# 3_waffling60-MXHS-ANSI_mcu.net
KiCad netlist of a schematic drawn in Altium Designer
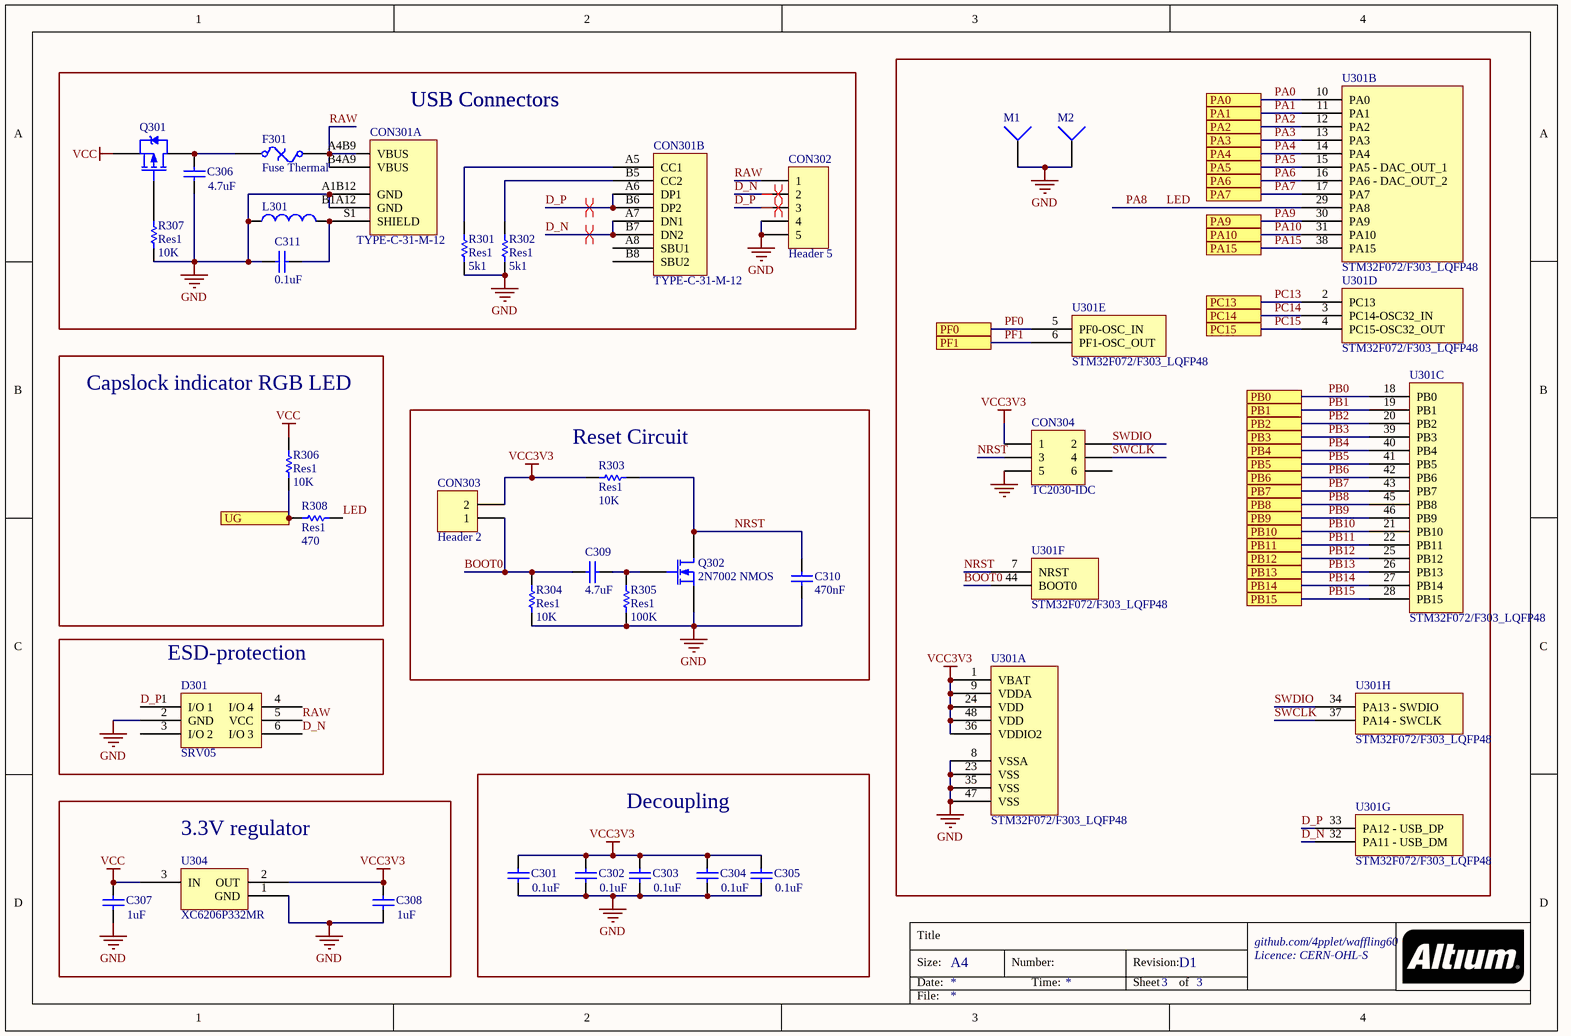
[diagram p0: 3_waffling60-MXHS-ANSI_mcu.SchDoc]

(export (version "E")
  (design (tool "Eeschema 10.0.6"))
  (components
    (comp (ref "C301")
      (value "0.1uF")
      (footprint "C0603[1608]")
      (description "Capacitor")
      (fields (field (name "LCSC PART #") "C14663") (field (name "MRF.PART") "CC0603KRX7R9BB104"))
      (libsource (lib "Miscellaneous Devices") (part "Cap"))
    )
    (comp (ref "C302")
      (value "0.1uF")
      (footprint "C0603[1608]")
      (description "Capacitor")
      (fields (field (name "LCSC PART #") "C14663") (field (name "MRF.PART") "CC0603KRX7R9BB104"))
      (libsource (lib "Miscellaneous Devices") (part "Cap"))
    )
    (comp (ref "C303")
      (value "0.1uF")
      (footprint "C0603[1608]")
      (description "Capacitor")
      (fields (field (name "LCSC PART #") "C14663") (field (name "MRF.PART") "CC0603KRX7R9BB104"))
      (libsource (lib "Miscellaneous Devices") (part "Cap"))
    )
    (comp (ref "C304")
      (value "0.1uF")
      (footprint "C0603[1608]")
      (description "Capacitor")
      (fields (field (name "LCSC PART #") "C14663") (field (name "MRF.PART") "CC0603KRX7R9BB104"))
      (libsource (lib "Miscellaneous Devices") (part "Cap"))
    )
    (comp (ref "C305")
      (value "0.1uF")
      (footprint "C0603[1608]")
      (description "Capacitor")
      (fields (field (name "LCSC PART #") "C14663") (field (name "MRF.PART") "CC0603KRX7R9BB104"))
      (libsource (lib "Miscellaneous Devices") (part "Cap"))
    )
    (comp (ref "C306")
      (value "4.7uF")
      (footprint "C0603[1608]")
      (description "Capacitor")
      (fields (field (name "LCSC PART #") "C19666") (field (name "MRF.PART") "CL10A475KO8NNNC"))
      (libsource (lib "Miscellaneous Devices") (part "Cap"))
    )
    (comp (ref "C307")
      (value "1uF")
      (footprint "C0603[1608]")
      (description "Capacitor")
      (fields (field (name "LCSC PART #") "C15849") (field (name "MRF.PART") "CL10A105KB8NNNC"))
      (libsource (lib "Miscellaneous Devices") (part "Cap"))
    )
    (comp (ref "C308")
      (value "1uF")
      (footprint "C0603[1608]")
      (description "Capacitor")
      (fields (field (name "LCSC PART #") "C15849") (field (name "MRF.PART") "CL10A105KB8NNNC"))
      (libsource (lib "Miscellaneous Devices") (part "Cap"))
    )
    (comp (ref "C309")
      (value "4.7uF")
      (footprint "C0603[1608]")
      (description "Capacitor")
      (fields (field (name "LCSC PART #") "C19666") (field (name "MRF.PART") "CL10A475KO8NNNC"))
      (libsource (lib "Miscellaneous Devices") (part "Cap"))
    )
    (comp (ref "C310")
      (value "470nF")
      (footprint "C0603[1608]")
      (description "Capacitor")
      (fields (field (name "LCSC PART #") "C1623") (field (name "MRF.PART") "CL10B474KA8NNNC"))
      (libsource (lib "Miscellaneous Devices") (part "Cap"))
    )
    (comp (ref "C311")
      (value "0.1uF")
      (footprint "C0603[1608]")
      (description "Capacitor")
      (fields (field (name "LCSC PART #") "C14663") (field (name "MRF.PART") "CC0603KRX7R9BB104"))
      (libsource (lib "Miscellaneous Devices") (part "Cap"))
    )
    (comp (ref "CON301")
      (value "TYPE-C-31-M-12")
      (footprint "TYPE-C-31-M-12")
      (fields (field (name "LCSC PART #") "C165948"))
      (libsource (lib "Schlib1") (part "TYPE-C-31-M-12"))
    )
    (comp (ref "CON302")
      (value "Header 5")
      (footprint "UDB_combo_JST_MOLEX")
      (description "JST for USB daughter board")
      (fields (field (name "LCSC PART #") "C145956"))
      (libsource (lib "Miscellaneous Connectors") (part "Header 5"))
    )
    (comp (ref "CON303")
      (value "Header 2")
      (footprint "HDR1X2")
      (description "Header, 2-Pin")
      (libsource (lib "Miscellaneous Connectors") (part "Header 2"))
    )
    (comp (ref "CON304")
      (value "TC2030-IDC")
      (footprint "TC2030-IDC-NL")
      (description "Header, 3-Pin, Dual row")
      (libsource (lib "Miscellaneous Connectors") (part "Header 3X2"))
    )
    (comp (ref "D301")
      (value "SRV05")
      (footprint "SOT-23-6")
      (fields (field (name "LCSC PART #") "C85364") (field (name "MRF.PART") "SRV05-4-P-T7"))
      (libsource (lib "Keebs") (part "SRV05"))
    )
    (comp (ref "F301")
      (value "Fuse Thermal")
      (footprint "C1206[3216]")
      (description "Thermal Fuse")
      (fields (field (name "LCSC PART #") "C135338") (field (name "MRF.PART") "ASMD1206-050"))
      (libsource (lib "Miscellaneous Devices") (part "Fuse Thermal"))
    )
    (comp (ref "L301")
      (value "Inductor")
      (footprint "L0805")
      (fields (field (name "LCSC PART #") "C1015") (field (name "MRF.PART") "GZ2012D101TF"))
      (libsource (lib "Simulation Generic Components") (part "Inductor"))
    )
    (comp (ref "M1")
      (value "Socket")
      (footprint "mounting_hole")
      (libsource (lib "Miscellaneous Connectors") (part "Socket"))
    )
    (comp (ref "M2")
      (value "Socket")
      (footprint "mounting_hole")
      (libsource (lib "Miscellaneous Connectors") (part "Socket"))
    )
    (comp (ref "Q301")
      (value "PMOS-2")
      (footprint "SOT-23-3")
      (description "P-Channel Power MOSFET")
      (fields (field (name "LCSC PART #") "C10487") (field (name "MRF.PART") "SI2301CDS-T1-GE3"))
      (libsource (lib "Miscellaneous Devices") (part "PMOS-2"))
    )
    (comp (ref "Q302")
      (value "2N7002 NMOS")
      (footprint "SOT-23-3")
      (description "N-Channel MOSFET")
      (fields (field (name "LCSC PART #") "C8545") (field (name "MRF.PART") "2N7002"))
      (libsource (lib "Miscellaneous Devices") (part "MOSFET-N"))
    )
    (comp (ref "R301")
      (value "Res1")
      (footprint "R0603[1608]")
      (description "Resistor")
      (fields
        (field (name "ALTIUM_VALUE") "5k1")
        (field (name "LCSC PART #") "C23186")
        (field (name "MRF.PART") "0603WAF5101T5E")
      )
      (libsource (lib "Miscellaneous Devices") (part "Res1"))
    )
    (comp (ref "R302")
      (value "Res1")
      (footprint "R0603[1608]")
      (description "Resistor")
      (fields
        (field (name "ALTIUM_VALUE") "5k1")
        (field (name "LCSC PART #") "C23186")
        (field (name "MRF.PART") "0603WAF5101T5E")
      )
      (libsource (lib "Miscellaneous Devices") (part "Res1"))
    )
    (comp (ref "R303")
      (value "Res1")
      (footprint "R0603[1608]")
      (description "Resistor")
      (fields
        (field (name "ALTIUM_VALUE") "10K")
        (field (name "LCSC PART #") "C25804")
        (field (name "MRF.PART") "0603WAF1002T5E")
      )
      (libsource (lib "Miscellaneous Devices") (part "Res1"))
    )
    (comp (ref "R304")
      (value "Res1")
      (footprint "R0603[1608]")
      (description "Resistor")
      (fields
        (field (name "ALTIUM_VALUE") "10K")
        (field (name "LCSC PART #") "C25804")
        (field (name "MRF.PART") "0603WAF1002T5E")
      )
      (libsource (lib "Miscellaneous Devices") (part "Res1"))
    )
    (comp (ref "R305")
      (value "Res1")
      (footprint "R0603[1608]")
      (description "Resistor")
      (fields
        (field (name "ALTIUM_VALUE") "100K")
        (field (name "LCSC PART #") "C25803")
        (field (name "MRF.PART") "0603WAF1003T5E")
      )
      (libsource (lib "Miscellaneous Devices") (part "Res1"))
    )
    (comp (ref "R306")
      (value "Res1")
      (footprint "R0603[1608]")
      (description "Resistor")
      (fields
        (field (name "ALTIUM_VALUE") "10K")
        (field (name "LCSC PART #") "C25804")
        (field (name "MRF.PART") "0603WAF1002T5E")
      )
      (libsource (lib "Miscellaneous Devices") (part "Res1"))
    )
    (comp (ref "R307")
      (value "Res1")
      (footprint "R0603[1608]")
      (description "Resistor")
      (fields
        (field (name "ALTIUM_VALUE") "10K")
        (field (name "LCSC PART #") "C25804")
        (field (name "MRF.PART") "0603WAF1002T5E")
      )
      (libsource (lib "Miscellaneous Devices") (part "Res1"))
    )
    (comp (ref "R308")
      (value "Res1")
      (footprint "R0603[1608]")
      (description "Resistor")
      (fields
        (field (name "ALTIUM_VALUE") "470")
        (field (name "LCSC PART #") "C23179")
        (field (name "MRF.PART") "0603WAF4700T5E")
      )
      (libsource (lib "Miscellaneous Devices") (part "Res1"))
    )
    (comp (ref "U301")
      (value "STM32F072/F303_LQFP48")
      (footprint "STM32 - COMBO 7X7MM")
      (fields (field (name "LCSC PART #") "C915660") (field (name "MRF.PART") "APM32F072CBT6"))
      (libsource (lib "Keebs") (part "STM32F072/F303_LQFP48"))
    )
    (comp (ref "U304")
      (value "XC6206P332MR")
      (footprint "SOT-23-3")
      (fields (field (name "LCSC PART #") "C5446"))
      (libsource (lib "Keebs") (part "SOT23 LDO"))
    )
  )
  (nets
    (net (code "1") (name "/BOOT0") (class "Default")
      (node (ref "C309") (pin "1") (pinfunction "1_1") (pintype "passive"))
      (node (ref "CON303") (pin "1") (pinfunction "1_1") (pintype "passive"))
      (node (ref "R304") (pin "1") (pinfunction "1_1") (pintype "passive"))
      (node (ref "U301") (pin "44") (pinfunction "BOOT0_44") (pintype "passive"))
    )
    (net (code "2") (name "/D_N") (class "Default")
      (node (ref "CON301") (pin "A7") (pinfunction "DN1_A7") (pintype "passive"))
      (node (ref "CON301") (pin "B7") (pinfunction "DN2_B7") (pintype "passive"))
      (node (ref "CON302") (pin "2") (pinfunction "2_2") (pintype "passive"))
      (node (ref "D301") (pin "6") (pinfunction "I/O_3_6") (pintype "passive"))
      (node (ref "U301") (pin "32") (pinfunction "PA11_-_USB_DM_32") (pintype "passive"))
    )
    (net (code "3") (name "/D_P") (class "Default")
      (node (ref "CON301") (pin "A6") (pinfunction "DP1_A6") (pintype "passive"))
      (node (ref "CON301") (pin "B6") (pinfunction "DP2_B6") (pintype "passive"))
      (node (ref "CON302") (pin "3") (pinfunction "3_3") (pintype "passive"))
      (node (ref "D301") (pin "1") (pinfunction "I/O_1_1") (pintype "passive"))
      (node (ref "U301") (pin "33") (pinfunction "PA12_-_USB_DP_33") (pintype "passive"))
    )
    (net (code "4") (name "/LED") (class "Default")
      (node (ref "R308") (pin "2") (pinfunction "2_2") (pintype "passive"))
      (node (ref "U301") (pin "29") (pinfunction "PA8_29") (pintype "passive"))
    )
    (net (code "5") (name "/NRST") (class "Default")
      (node (ref "C310") (pin "1") (pinfunction "1_1") (pintype "passive"))
      (node (ref "CON304") (pin "3") (pinfunction "3_3") (pintype "passive"))
      (node (ref "Q302") (pin "3") (pinfunction "D_3") (pintype "passive"))
      (node (ref "R303") (pin "2") (pinfunction "2_2") (pintype "passive"))
      (node (ref "U301") (pin "7") (pinfunction "NRST_7") (pintype "passive"))
    )
    (net (code "6") (name "/PA0") (class "Default")
      (node (ref "U301") (pin "10") (pinfunction "PA0_10") (pintype "passive"))
    )
    (net (code "7") (name "/PA1") (class "Default")
      (node (ref "U301") (pin "11") (pinfunction "PA1_11") (pintype "passive"))
    )
    (net (code "8") (name "/PA2") (class "Default")
      (node (ref "U301") (pin "12") (pinfunction "PA2_12") (pintype "passive"))
    )
    (net (code "9") (name "/PA3") (class "Default")
      (node (ref "U301") (pin "13") (pinfunction "PA3_13") (pintype "passive"))
    )
    (net (code "10") (name "/PA4") (class "Default")
      (node (ref "U301") (pin "14") (pinfunction "PA4_14") (pintype "passive"))
    )
    (net (code "11") (name "/PA5") (class "Default")
      (node (ref "U301") (pin "15") (pinfunction "PA5_-_DAC_OUT_1_15") (pintype "passive"))
    )
    (net (code "12") (name "/PA6") (class "Default")
      (node (ref "U301") (pin "16") (pinfunction "PA6_-_DAC_OUT_2_16") (pintype "passive"))
    )
    (net (code "13") (name "/PA7") (class "Default")
      (node (ref "U301") (pin "17") (pinfunction "PA7_17") (pintype "passive"))
    )
    (net (code "14") (name "/PA9") (class "Default")
      (node (ref "U301") (pin "30") (pinfunction "PA9_30") (pintype "passive"))
    )
    (net (code "15") (name "/PA10") (class "Default")
      (node (ref "U301") (pin "31") (pinfunction "PA10_31") (pintype "passive"))
    )
    (net (code "16") (name "/PA15") (class "Default")
      (node (ref "U301") (pin "38") (pinfunction "PA15_38") (pintype "passive"))
    )
    (net (code "17") (name "/PB0") (class "Default")
      (node (ref "U301") (pin "18") (pinfunction "PB0_18") (pintype "passive"))
    )
    (net (code "18") (name "/PB1") (class "Default")
      (node (ref "U301") (pin "19") (pinfunction "PB1_19") (pintype "passive"))
    )
    (net (code "19") (name "/PB2") (class "Default")
      (node (ref "U301") (pin "20") (pinfunction "PB2_20") (pintype "passive"))
    )
    (net (code "20") (name "/PB3") (class "Default")
      (node (ref "U301") (pin "39") (pinfunction "PB3_39") (pintype "passive"))
    )
    (net (code "21") (name "/PB4") (class "Default")
      (node (ref "U301") (pin "40") (pinfunction "PB4_40") (pintype "passive"))
    )
    (net (code "22") (name "/PB5") (class "Default")
      (node (ref "U301") (pin "41") (pinfunction "PB5_41") (pintype "passive"))
    )
    (net (code "23") (name "/PB6") (class "Default")
      (node (ref "U301") (pin "42") (pinfunction "PB6_42") (pintype "passive"))
    )
    (net (code "24") (name "/PB7") (class "Default")
      (node (ref "U301") (pin "43") (pinfunction "PB7_43") (pintype "passive"))
    )
    (net (code "25") (name "/PB8") (class "Default")
      (node (ref "U301") (pin "45") (pinfunction "PB8_45") (pintype "passive"))
    )
    (net (code "26") (name "/PB9") (class "Default")
      (node (ref "U301") (pin "46") (pinfunction "PB9_46") (pintype "passive"))
    )
    (net (code "27") (name "/PB10") (class "Default")
      (node (ref "U301") (pin "21") (pinfunction "PB10_21") (pintype "passive"))
    )
    (net (code "28") (name "/PB11") (class "Default")
      (node (ref "U301") (pin "22") (pinfunction "PB11_22") (pintype "passive"))
    )
    (net (code "29") (name "/PB12") (class "Default")
      (node (ref "U301") (pin "25") (pinfunction "PB12_25") (pintype "passive"))
    )
    (net (code "30") (name "/PB13") (class "Default")
      (node (ref "U301") (pin "26") (pinfunction "PB13_26") (pintype "passive"))
    )
    (net (code "31") (name "/PB14") (class "Default")
      (node (ref "U301") (pin "27") (pinfunction "PB14_27") (pintype "passive"))
    )
    (net (code "32") (name "/PB15") (class "Default")
      (node (ref "U301") (pin "28") (pinfunction "PB15_28") (pintype "passive"))
    )
    (net (code "33") (name "/PC13") (class "Default")
      (node (ref "U301") (pin "2") (pinfunction "PC13_2") (pintype "passive"))
    )
    (net (code "34") (name "/PC14") (class "Default")
      (node (ref "U301") (pin "3") (pinfunction "PC14-OSC32_IN_3") (pintype "passive"))
    )
    (net (code "35") (name "/PC15") (class "Default")
      (node (ref "U301") (pin "4") (pinfunction "PC15-OSC32_OUT_4") (pintype "passive"))
    )
    (net (code "36") (name "/PF0") (class "Default")
      (node (ref "U301") (pin "5") (pinfunction "PF0-OSC_IN_5") (pintype "passive"))
    )
    (net (code "37") (name "/PF1") (class "Default")
      (node (ref "U301") (pin "6") (pinfunction "PF1-OSC_OUT_6") (pintype "passive"))
    )
    (net (code "38") (name "/RAW") (class "Default")
      (node (ref "CON301") (pin "A4B9") (pinfunction "VBUS_A4B9") (pintype "passive"))
      (node (ref "CON301") (pin "B4A9") (pinfunction "VBUS_B4A9") (pintype "passive"))
      (node (ref "CON302") (pin "1") (pinfunction "1_1") (pintype "passive"))
      (node (ref "D301") (pin "5") (pinfunction "VCC_5") (pintype "passive"))
      (node (ref "F301") (pin "2") (pinfunction "2_2") (pintype "passive"))
    )
    (net (code "39") (name "/SWCLK") (class "Default")
      (node (ref "CON304") (pin "4") (pinfunction "4_4") (pintype "passive"))
      (node (ref "U301") (pin "37") (pinfunction "PA14_-_SWCLK_37") (pintype "passive"))
    )
    (net (code "40") (name "/SWDIO") (class "Default")
      (node (ref "CON304") (pin "2") (pinfunction "2_2") (pintype "passive"))
      (node (ref "U301") (pin "34") (pinfunction "PA13_-_SWDIO_34") (pintype "passive"))
    )
    (net (code "41") (name "/UG") (class "Default")
      (node (ref "R306") (pin "2") (pinfunction "2_2") (pintype "passive"))
      (node (ref "R308") (pin "1") (pinfunction "1_1") (pintype "passive"))
    )
    (net (code "42") (name "GND") (class "Default")
      (node (ref "C301") (pin "1") (pinfunction "1_1") (pintype "passive"))
      (node (ref "C302") (pin "1") (pinfunction "1_1") (pintype "passive"))
      (node (ref "C303") (pin "1") (pinfunction "1_1") (pintype "passive"))
      (node (ref "C304") (pin "1") (pinfunction "1_1") (pintype "passive"))
      (node (ref "C305") (pin "1") (pinfunction "1_1") (pintype "passive"))
      (node (ref "C306") (pin "1") (pinfunction "1_1") (pintype "passive"))
      (node (ref "C307") (pin "1") (pinfunction "1_1") (pintype "passive"))
      (node (ref "C308") (pin "1") (pinfunction "1_1") (pintype "passive"))
      (node (ref "C310") (pin "2") (pinfunction "2_2") (pintype "passive"))
      (node (ref "C311") (pin "1") (pinfunction "1_1") (pintype "passive"))
      (node (ref "CON301") (pin "A1B12") (pinfunction "GND_A1B12") (pintype "passive"))
      (node (ref "CON301") (pin "B1A12") (pinfunction "GND_B1A12") (pintype "passive"))
      (node (ref "CON302") (pin "4") (pinfunction "4_4") (pintype "passive"))
      (node (ref "CON302") (pin "5") (pinfunction "5_5") (pintype "passive"))
      (node (ref "CON304") (pin "5") (pinfunction "5_5") (pintype "passive"))
      (node (ref "D301") (pin "2") (pinfunction "GND_2") (pintype "passive"))
      (node (ref "L301") (pin "1") (pinfunction "1_1") (pintype "passive"))
      (node (ref "M1") (pin "1") (pinfunction "1_1") (pintype "passive"))
      (node (ref "M2") (pin "1") (pinfunction "1_1") (pintype "passive"))
      (node (ref "Q302") (pin "2") (pinfunction "S_2") (pintype "passive"))
      (node (ref "R301") (pin "2") (pinfunction "2_2") (pintype "passive"))
      (node (ref "R302") (pin "2") (pinfunction "2_2") (pintype "passive"))
      (node (ref "R304") (pin "2") (pinfunction "2_2") (pintype "passive"))
      (node (ref "R305") (pin "2") (pinfunction "2_2") (pintype "passive"))
      (node (ref "R307") (pin "2") (pinfunction "2_2") (pintype "passive"))
      (node (ref "U301") (pin "23") (pinfunction "VSS_23") (pintype "passive"))
      (node (ref "U301") (pin "35") (pinfunction "VSS_35") (pintype "passive"))
      (node (ref "U301") (pin "47") (pinfunction "VSS_47") (pintype "passive"))
      (node (ref "U301") (pin "8") (pinfunction "VSSA_8") (pintype "passive"))
      (node (ref "U304") (pin "1") (pinfunction "GND_1") (pintype "passive"))
    )
    (net (code "43") (name "Net-(CON301A-SHIELD)") (class "Default")
      (node (ref "C311") (pin "2") (pinfunction "2_2") (pintype "passive"))
      (node (ref "CON301") (pin "S1") (pinfunction "SHIELD_S1") (pintype "passive"))
      (node (ref "L301") (pin "2") (pinfunction "2_2") (pintype "passive"))
    )
    (net (code "44") (name "Net-(CON301B-CC1)") (class "Default")
      (node (ref "CON301") (pin "A5") (pinfunction "CC1_A5") (pintype "passive"))
      (node (ref "R301") (pin "1") (pinfunction "1_1") (pintype "passive"))
    )
    (net (code "45") (name "Net-(CON301B-CC2)") (class "Default")
      (node (ref "CON301") (pin "B5") (pinfunction "CC2_B5") (pintype "passive"))
      (node (ref "R302") (pin "1") (pinfunction "1_1") (pintype "passive"))
    )
    (net (code "46") (name "Net-(Q301-D)") (class "Default")
      (node (ref "C306") (pin "2") (pinfunction "2_2") (pintype "passive"))
      (node (ref "F301") (pin "1") (pinfunction "1_1") (pintype "passive"))
      (node (ref "Q301") (pin "3") (pinfunction "D_3") (pintype "passive"))
    )
    (net (code "47") (name "Net-(Q301-G)") (class "Default")
      (node (ref "Q301") (pin "1") (pinfunction "G_1") (pintype "passive"))
      (node (ref "R307") (pin "1") (pinfunction "1_1") (pintype "passive"))
    )
    (net (code "48") (name "Net-(Q302-G)") (class "Default")
      (node (ref "C309") (pin "2") (pinfunction "2_2") (pintype "passive"))
      (node (ref "Q302") (pin "1") (pinfunction "G_1") (pintype "passive"))
      (node (ref "R305") (pin "1") (pinfunction "1_1") (pintype "passive"))
    )
    (net (code "49") (name "VCC") (class "Default")
      (node (ref "C307") (pin "2") (pinfunction "2_2") (pintype "passive"))
      (node (ref "Q301") (pin "2") (pinfunction "S_2") (pintype "passive"))
      (node (ref "R306") (pin "1") (pinfunction "1_1") (pintype "passive"))
      (node (ref "U304") (pin "3") (pinfunction "IN_3") (pintype "passive"))
    )
    (net (code "50") (name "VCC3V3") (class "Default")
      (node (ref "C301") (pin "2") (pinfunction "2_2") (pintype "passive"))
      (node (ref "C302") (pin "2") (pinfunction "2_2") (pintype "passive"))
      (node (ref "C303") (pin "2") (pinfunction "2_2") (pintype "passive"))
      (node (ref "C304") (pin "2") (pinfunction "2_2") (pintype "passive"))
      (node (ref "C305") (pin "2") (pinfunction "2_2") (pintype "passive"))
      (node (ref "C308") (pin "2") (pinfunction "2_2") (pintype "passive"))
      (node (ref "CON303") (pin "2") (pinfunction "2_2") (pintype "passive"))
      (node (ref "CON304") (pin "1") (pinfunction "1_1") (pintype "passive"))
      (node (ref "R303") (pin "1") (pinfunction "1_1") (pintype "passive"))
      (node (ref "U301") (pin "1") (pinfunction "VBAT_1") (pintype "passive"))
      (node (ref "U301") (pin "24") (pinfunction "VDD_24") (pintype "passive"))
      (node (ref "U301") (pin "36") (pinfunction "VDDIO2_36") (pintype "passive"))
      (node (ref "U301") (pin "48") (pinfunction "VDD_48") (pintype "passive"))
      (node (ref "U301") (pin "9") (pinfunction "VDDA_9") (pintype "passive"))
      (node (ref "U304") (pin "2") (pinfunction "OUT_2") (pintype "passive"))
    )
    (net (code "51") (name "unconnected-(CON301B-SBU1-PadA8)") (class "Default")
      (node (ref "CON301") (pin "A8") (pinfunction "SBU1_A8") (pintype "passive"))
    )
    (net (code "52") (name "unconnected-(CON301B-SBU2-PadB8)") (class "Default")
      (node (ref "CON301") (pin "B8") (pinfunction "SBU2_B8") (pintype "passive"))
    )
    (net (code "53") (name "unconnected-(CON304-Pad6)") (class "Default")
      (node (ref "CON304") (pin "6") (pinfunction "6_6") (pintype "passive"))
    )
    (net (code "54") (name "unconnected-(D301-I{slash}O_2-Pad3)") (class "Default")
      (node (ref "D301") (pin "3") (pinfunction "I/O_2_3") (pintype "passive"))
    )
    (net (code "55") (name "unconnected-(D301-I{slash}O_4-Pad4)") (class "Default")
      (node (ref "D301") (pin "4") (pinfunction "I/O_4_4") (pintype "passive"))
    )
  )
)
